# main.net
KiCad netlist of a schematic drawn in Altium Designer
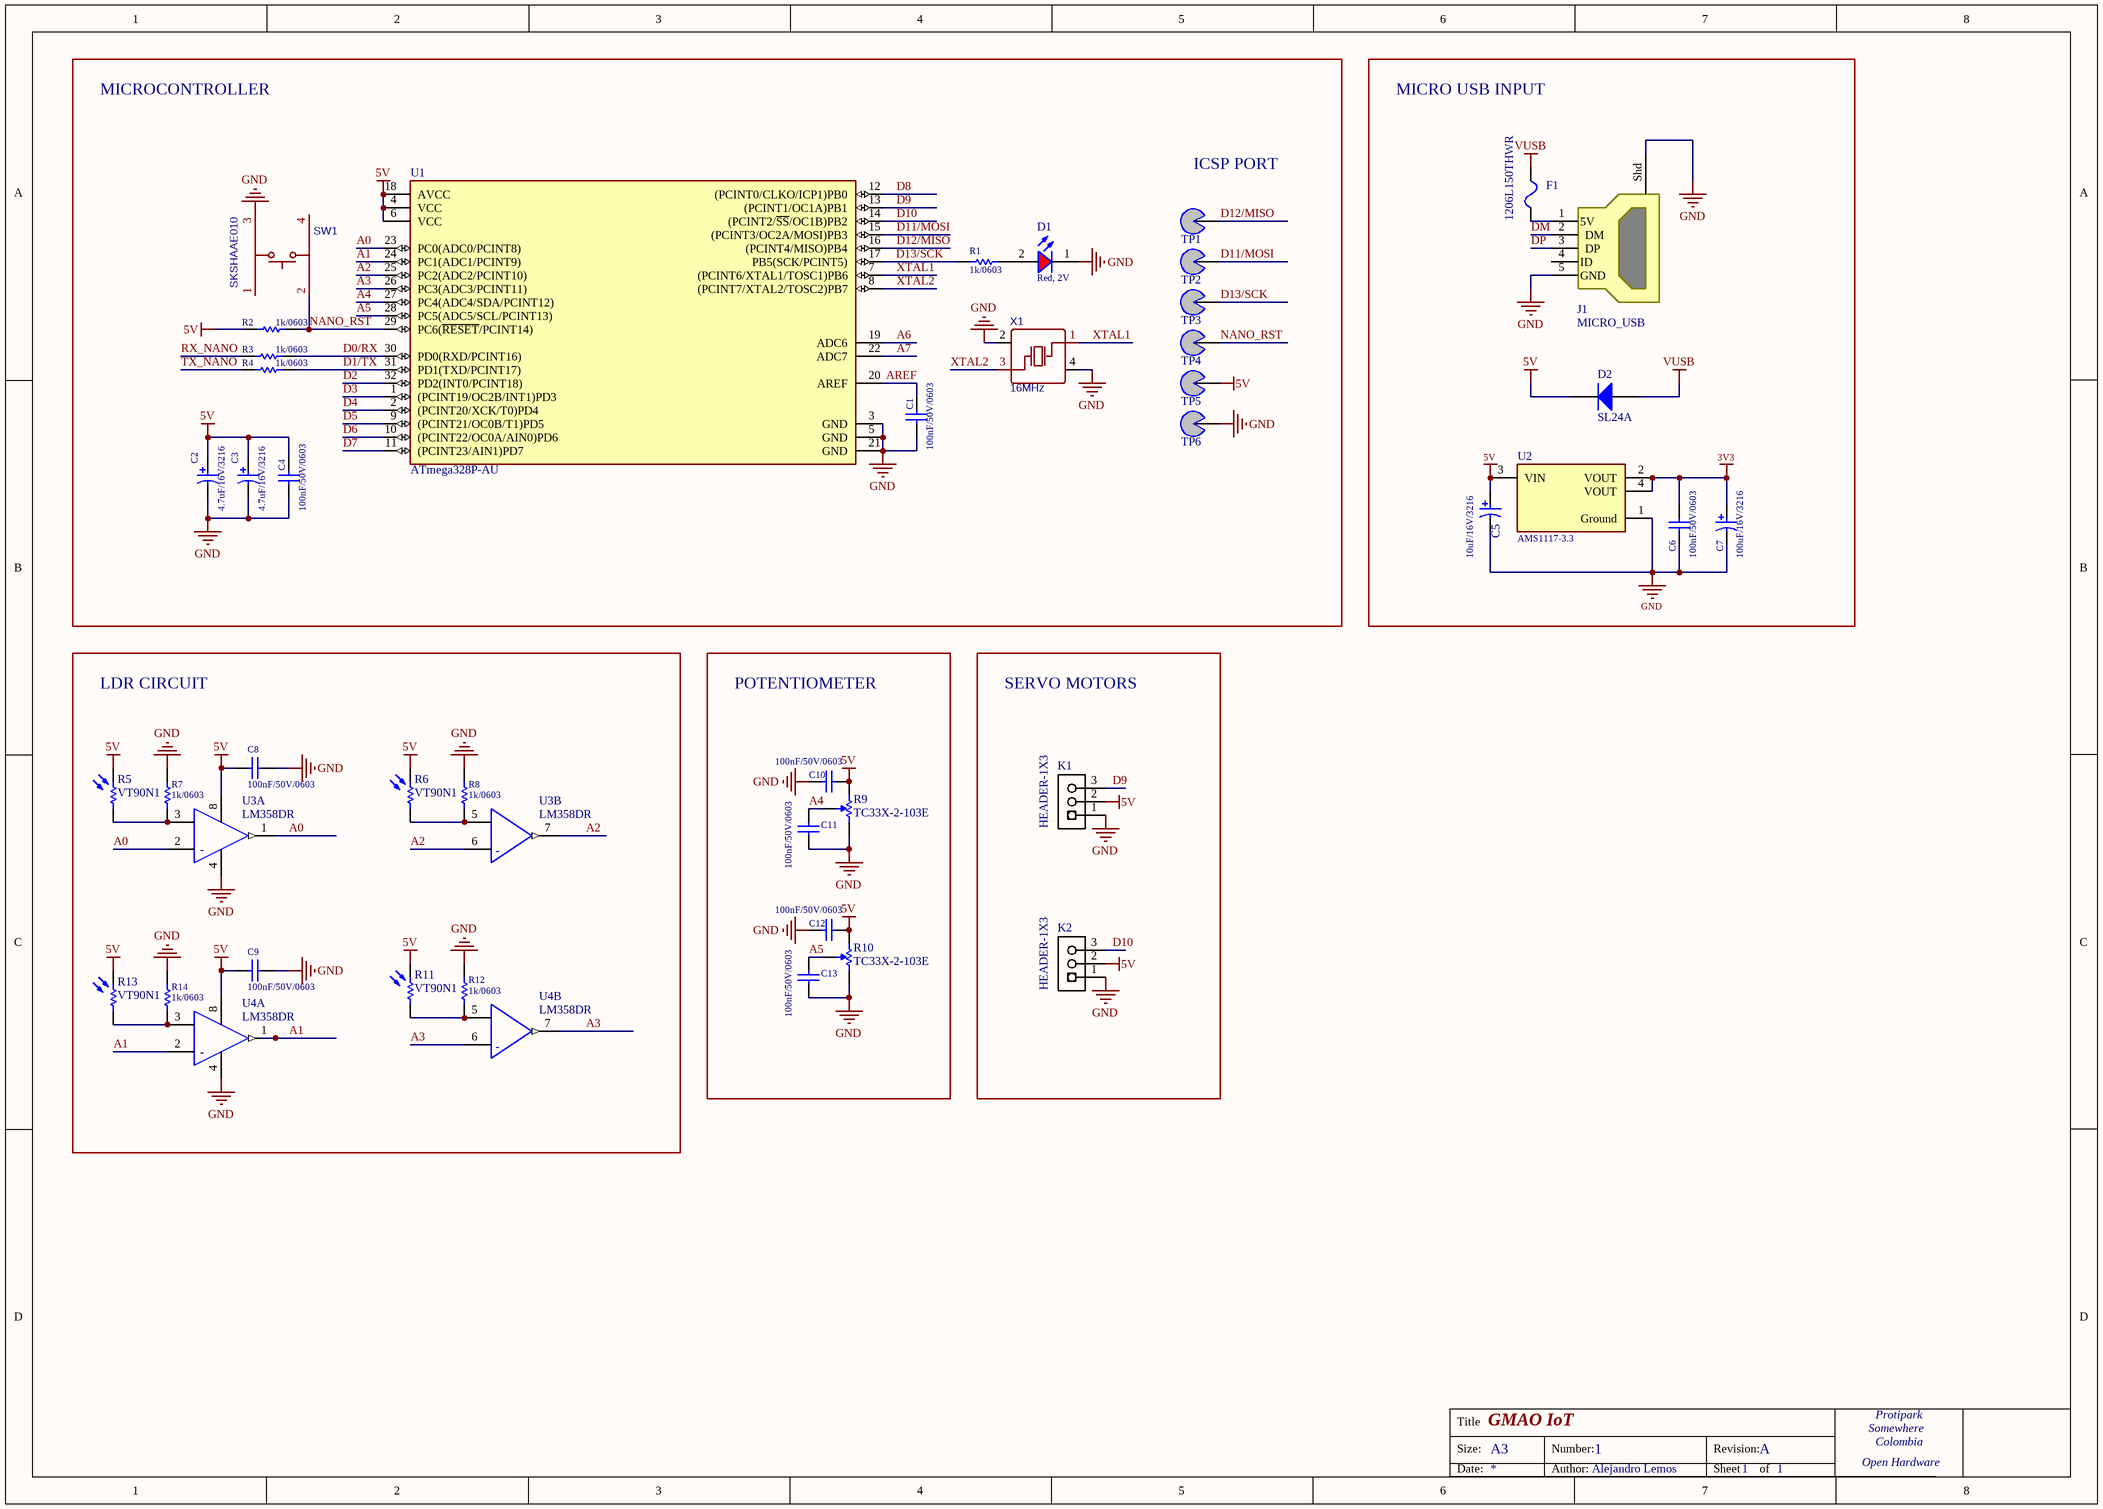
[diagram p0: main.SchDoc]

(export (version "E")
  (design (tool "Eeschema 10.0.6"))
  (components
    (comp (ref "C1")
      (value "100nF/50V/0603")
      (footprint "C0603_L")
      (libsource (lib "seitechs") (part "C_SMD"))
    )
    (comp (ref "C2")
      (value "4.7uF/16V/3216")
      (footprint "KEMT-T491-A_L")
      (description "Tantalum Capacitor, 2.2 uF, +/- 10%, 16 V, -55 to 125 degC, 2-Pin SMD, RoHS, Tape and Reel")
      (fields (field (name "VOLTAGE") "16VDC") (field (name "MANUFACTURER") "Kemet"))
      (libsource (lib "Altium Content Vault") (part "CAP-P-2"))
    )
    (comp (ref "C3")
      (value "4.7uF/16V/3216")
      (footprint "KEMT-T491-A_L")
      (description "Tantalum Capacitor, 2.2 uF, +/- 10%, 16 V, -55 to 125 degC, 2-Pin SMD, RoHS, Tape and Reel")
      (fields (field (name "VOLTAGE") "16VDC") (field (name "MANUFACTURER") "Kemet"))
      (libsource (lib "Altium Content Vault") (part "CAP-P-2"))
    )
    (comp (ref "C4")
      (value "100nF/50V/0603")
      (footprint "C0603_L")
      (libsource (lib "seitechs") (part "C_SMD"))
    )
    (comp (ref "C5")
      (value "10uF/16V/3216")
      (footprint "KEMT-T491-A_L")
      (description "Tantalum Capacitor, 2.2 uF, +/- 10%, 16 V, -55 to 125 degC, 2-Pin SMD, RoHS, Tape and Reel")
      (fields (field (name "VOLTAGE") "16VDC") (field (name "MANUFACTURER") "Kemet"))
      (libsource (lib "Altium Content Vault") (part "CAP-P-2"))
    )
    (comp (ref "C6")
      (value "100nF/50V/0603")
      (footprint "C0603_L")
      (libsource (lib "seitechs") (part "C_SMD"))
    )
    (comp (ref "C7")
      (value "100uF/16V/3216")
      (footprint "KEMT-T491-A_L")
      (description "Tantalum Capacitor, 2.2 uF, +/- 10%, 16 V, -55 to 125 degC, 2-Pin SMD, RoHS, Tape and Reel")
      (fields (field (name "VOLTAGE") "16VDC") (field (name "MANUFACTURER") "Kemet"))
      (libsource (lib "Altium Content Vault") (part "CAP-P-2"))
    )
    (comp (ref "C8")
      (value "100nF/50V/0603")
      (footprint "C0603_L")
      (libsource (lib "seitechs") (part "C_SMD"))
    )
    (comp (ref "C9")
      (value "100nF/50V/0603")
      (footprint "C0603_L")
      (libsource (lib "seitechs") (part "C_SMD"))
    )
    (comp (ref "C10")
      (value "100nF/50V/0603")
      (footprint "C0603_L")
      (libsource (lib "seitechs") (part "C_SMD"))
    )
    (comp (ref "C11")
      (value "100nF/50V/0603")
      (footprint "C0603_L")
      (libsource (lib "seitechs") (part "C_SMD"))
    )
    (comp (ref "C12")
      (value "100nF/50V/0603")
      (footprint "C0603_L")
      (libsource (lib "seitechs") (part "C_SMD"))
    )
    (comp (ref "C13")
      (value "100nF/50V/0603")
      (footprint "C0603_L")
      (libsource (lib "seitechs") (part "C_SMD"))
    )
    (comp (ref "D1")
      (value "Red, 2V")
      (footprint "WL-SMCW_0603_H=0.7mm")
      (description "WL-SMCW SMT Mono-color Chip LED Waterclear, size 0603, Red, 2V, 140deg")
      (fields (field (name "PART NUMBER") "150060RS75000") (field (name "PUBLISHER") "Wurth Elektronik"))
      (libsource (lib "Altium_WL-SMCW (rev20a)") (part "150060RS75000"))
    )
    (comp (ref "D2")
      (value "SL24A")
      (footprint "GESC-GAP3SLT33-214-2_V")
      (description "40V 2A 420mV @ 2A SMA(DO-214AC) Schottky Barrier Diodes (SBD) RoHS")
      (fields (field (name "MANUFACTURER") "GeneSiCSemiconductor"))
      (libsource (lib "Altium Content Vault") (part "D-AK-2"))
    )
    (comp (ref "F1")
      (value "1206L150THWR")
      (footprint "R1206_L")
      (description "FUSE PTC RESET 8V 1.50A 1206")
      (fields (field (name "MANUFACTURER") "Littelfuse Inc"))
      (libsource (lib "seitechs") (part "1206L150THWR"))
    )
    (comp (ref "J1")
      (value "MICRO_USB")
      (footprint "USB MICRO")
      (description "CONN USB MICRO B RECPT SMT R/A")
      (fields (field (name "MANUFACTURER") "FCI") (field (name "MANUFACTURER PART NUMBER") "10118194-0001LF"))
      (libsource (lib "seitechs") (part "MICRO_USB"))
    )
    (comp (ref "K1")
      (value "HEADER-1X3")
      (footprint "HEADER-1X3")
      (libsource (lib "vh_altium_library") (part "HEADER-1X3"))
    )
    (comp (ref "K2")
      (value "HEADER-1X3")
      (footprint "HEADER-1X3")
      (libsource (lib "vh_altium_library") (part "HEADER-1X3"))
    )
    (comp (ref "R1") (value "1k/0603") (footprint "R0603_N") (libsource (lib "seitechs") (part "R_SMD")))
    (comp (ref "R2") (value "1k/0603") (footprint "R0603_N") (libsource (lib "seitechs") (part "R_SMD")))
    (comp (ref "R3") (value "1k/0603") (footprint "R0603_N") (libsource (lib "seitechs") (part "R_SMD")))
    (comp (ref "R4") (value "1k/0603") (footprint "R0603_N") (libsource (lib "seitechs") (part "R_SMD")))
    (comp (ref "R5")
      (value "VT90N1")
      (footprint "EXCE-VT90N1")
      (description "Photoconductive Resistor, 200 kOhm, 100 V, 80 mW, -40 to 75 degC, 2-Pin THD, RoHS")
      (fields (field (name "MANUFACTURER") "Excelitas Technology"))
      (libsource (lib "Altium Content Vault") (part "PHOTO-RES-2"))
    )
    (comp (ref "R6")
      (value "VT90N1")
      (footprint "EXCE-VT90N1")
      (description "Photoconductive Resistor, 200 kOhm, 100 V, 80 mW, -40 to 75 degC, 2-Pin THD, RoHS")
      (fields (field (name "MANUFACTURER") "Excelitas Technology"))
      (libsource (lib "Altium Content Vault") (part "PHOTO-RES-2"))
    )
    (comp (ref "R7") (value "1k/0603") (footprint "R0603_N") (libsource (lib "seitechs") (part "R_SMD")))
    (comp (ref "R8") (value "1k/0603") (footprint "R0603_N") (libsource (lib "seitechs") (part "R_SMD")))
    (comp (ref "R9")
      (value "TC33X-2-103E")
      (footprint "BOUR-TC33X-2_V")
      (description "Trimming Potentiometer, 10000 Ohm, -40 to 100 degC, 3-Pin SMD, RoHS, Tape and Reel")
      (fields (field (name "TOLERANCE") "25%") (field (name "MANUFACTURER") "Bourns"))
      (libsource (lib "Altium Content Vault") (part "RES-ADJ-3_A"))
    )
    (comp (ref "R10")
      (value "TC33X-2-103E")
      (footprint "BOUR-TC33X-2_V")
      (description "Trimming Potentiometer, 10000 Ohm, -40 to 100 degC, 3-Pin SMD, RoHS, Tape and Reel")
      (fields (field (name "TOLERANCE") "25%") (field (name "MANUFACTURER") "Bourns"))
      (libsource (lib "Altium Content Vault") (part "RES-ADJ-3_A"))
    )
    (comp (ref "R11")
      (value "VT90N1")
      (footprint "EXCE-VT90N1")
      (description "Photoconductive Resistor, 200 kOhm, 100 V, 80 mW, -40 to 75 degC, 2-Pin THD, RoHS")
      (fields (field (name "MANUFACTURER") "Excelitas Technology"))
      (libsource (lib "Altium Content Vault") (part "PHOTO-RES-2"))
    )
    (comp (ref "R12") (value "1k/0603") (footprint "R0603_N") (libsource (lib "seitechs") (part "R_SMD")))
    (comp (ref "R13")
      (value "VT90N1")
      (footprint "EXCE-VT90N1")
      (description "Photoconductive Resistor, 200 kOhm, 100 V, 80 mW, -40 to 75 degC, 2-Pin THD, RoHS")
      (fields (field (name "MANUFACTURER") "Excelitas Technology"))
      (libsource (lib "Altium Content Vault") (part "PHOTO-RES-2"))
    )
    (comp (ref "R14") (value "1k/0603") (footprint "R0603_N") (libsource (lib "seitechs") (part "R_SMD")))
    (comp (ref "SW1")
      (value "SKSHAAE010")
      (footprint "SW-SMD_4P-L3.2-W2.9-P2.20-LS3.4")
      (description "SWITCH")
      (fields (field (name "BOM_SUPPLIER PART") "C262415") (field (name "CONTRIBUTOR") "LCSC"))
      (libsource (lib "seitechs") (part "SKSHAAE010"))
    )
    (comp (ref "TP1")
      (value "Test_Point")
      (footprint "TESTPOINT_PROG")
      (libsource (lib "seitechs") (part "Test_Point"))
    )
    (comp (ref "TP2")
      (value "Test_Point")
      (footprint "TESTPOINT_PROG")
      (libsource (lib "seitechs") (part "Test_Point"))
    )
    (comp (ref "TP3")
      (value "Test_Point")
      (footprint "TESTPOINT_PROG")
      (libsource (lib "seitechs") (part "Test_Point"))
    )
    (comp (ref "TP4")
      (value "Test_Point")
      (footprint "TESTPOINT_PROG")
      (libsource (lib "seitechs") (part "Test_Point"))
    )
    (comp (ref "TP5")
      (value "Test_Point")
      (footprint "TESTPOINT_PROG")
      (libsource (lib "seitechs") (part "Test_Point"))
    )
    (comp (ref "TP6")
      (value "Test_Point")
      (footprint "TESTPOINT_PROG")
      (libsource (lib "seitechs") (part "Test_Point"))
    )
    (comp (ref "U1")
      (value "ATmega328P-AU")
      (footprint "FP-32A-MFG")
      (description "IC MCU 8BIT 32KB FLASH 32TQFP")
      (fields
        (field (name "MANUFACTURER") "Microchip")
        (field (name "OCTOPART") "https://octopart.com/atmega328p-au-microchip-77760215")
      )
      (libsource (lib "Altium Content Vault") (part "f5fbdcb2c0c597ef7d3dd1575aef21a"))
    )
    (comp (ref "U2")
      (value "AMS1117-3.3")
      (footprint "FP-AMS1117-IPC_C")
      (description "LDO Voltage Regulators 1A, 3.3V")
      (fields
        (field (name "OCTOPART") "https://octopart.com/ams1117-3.3-advanced+monolithic+systems-25899300")
        (field (name "MANUFACTURER") "Advanced Monolithic Systems")
      )
      (libsource (lib "Altium Content Vault") (part "8bdbb5f8e77002000e30dd2845d0354"))
    )
    (comp (ref "U3")
      (value "LM358DR")
      (footprint "FP-D0008A-MFG")
      (description "IC OPAMP GP 2 CIRCUIT 8SOIC")
      (libsource (lib "Altium Content Vault") (part "0afdfe5f461d2cdd85604ff8654be97"))
    )
    (comp (ref "U4")
      (value "LM358DR")
      (footprint "FP-D0008A-MFG")
      (description "IC OPAMP GP 2 CIRCUIT 8SOIC")
      (libsource (lib "Altium Content Vault") (part "0afdfe5f461d2cdd85604ff8654be97"))
    )
    (comp (ref "X1")
      (value "16MHz")
      (footprint "CRYSTAL-SMD_4P-L3.2-W2.5-BL")
      (fields
        (field (name "BOM_MANUFACTURER PART") "X322516MOB4SI")
        (field (name "BOM_SUPPLIER PART") "C12668")
      )
      (libsource (lib "seitechs") (part "16MHz"))
    )
  )
  (nets
    (net (code "1") (name "/A0") (class "Default")
      (node (ref "U1") (pin "23") (pinfunction "PC0(ADC0/PCINT8)_23") (pintype "bidirectional"))
      (node (ref "U3") (pin "1") (pinfunction "1OUT_1") (pintype "output"))
      (node (ref "U3") (pin "2") (pinfunction "IN1-_2") (pintype "tri_state"))
    )
    (net (code "2") (name "/A1") (class "Default")
      (node (ref "U1") (pin "24") (pinfunction "PC1(ADC1/PCINT9)_24") (pintype "bidirectional"))
      (node (ref "U4") (pin "1") (pinfunction "1OUT_1") (pintype "output"))
      (node (ref "U4") (pin "2") (pinfunction "IN1-_2") (pintype "tri_state"))
    )
    (net (code "3") (name "/A2") (class "Default")
      (node (ref "U1") (pin "25") (pinfunction "PC2(ADC2/PCINT10)_25") (pintype "bidirectional"))
      (node (ref "U3") (pin "6") (pinfunction "IN2-_6") (pintype "tri_state"))
      (node (ref "U3") (pin "7") (pinfunction "2OUT_7") (pintype "output"))
    )
    (net (code "4") (name "/A3") (class "Default")
      (node (ref "U1") (pin "26") (pinfunction "PC3(ADC3/PCINT11)_26") (pintype "bidirectional"))
      (node (ref "U4") (pin "6") (pinfunction "IN2-_6") (pintype "tri_state"))
      (node (ref "U4") (pin "7") (pinfunction "2OUT_7") (pintype "output"))
    )
    (net (code "5") (name "/A4") (class "Default")
      (node (ref "C11") (pin "2") (pinfunction "2_2") (pintype "passive"))
      (node (ref "R9") (pin "2") (pinfunction "2_2") (pintype "passive"))
      (node (ref "U1") (pin "27") (pinfunction "PC4(ADC4/SDA/PCINT12)_27") (pintype "bidirectional"))
    )
    (net (code "6") (name "/A5") (class "Default")
      (node (ref "C13") (pin "2") (pinfunction "2_2") (pintype "passive"))
      (node (ref "R10") (pin "2") (pinfunction "2_2") (pintype "passive"))
      (node (ref "U1") (pin "28") (pinfunction "PC5(ADC5/SCL/PCINT13)_28") (pintype "bidirectional"))
    )
    (net (code "7") (name "/A6") (class "Default")
      (node (ref "U1") (pin "19") (pinfunction "ADC6_19") (pintype "power_in"))
    )
    (net (code "8") (name "/A7") (class "Default")
      (node (ref "U1") (pin "22") (pinfunction "ADC7_22") (pintype "passive"))
    )
    (net (code "9") (name "/AREF") (class "Default")
      (node (ref "C1") (pin "1") (pinfunction "1_1") (pintype "passive"))
      (node (ref "U1") (pin "20") (pinfunction "AREF_20") (pintype "passive"))
    )
    (net (code "10") (name "/D0{slash}RX") (class "Default")
      (node (ref "R3") (pin "2") (pinfunction "2_2") (pintype "passive"))
      (node (ref "U1") (pin "30") (pinfunction "PD0(RXD/PCINT16)_30") (pintype "bidirectional"))
    )
    (net (code "11") (name "/D1{slash}TX") (class "Default")
      (node (ref "R4") (pin "2") (pinfunction "2_2") (pintype "passive"))
      (node (ref "U1") (pin "31") (pinfunction "PD1(TXD/PCINT17)_31") (pintype "bidirectional"))
    )
    (net (code "12") (name "/D2") (class "Default")
      (node (ref "U1") (pin "32") (pinfunction "PD2(INT0/PCINT18)_32") (pintype "bidirectional"))
    )
    (net (code "13") (name "/D3") (class "Default")
      (node (ref "U1") (pin "1") (pinfunction "(PCINT19/OC2B/INT1)PD3_1") (pintype "bidirectional"))
    )
    (net (code "14") (name "/D4") (class "Default")
      (node (ref "U1") (pin "2") (pinfunction "(PCINT20/XCK/T0)PD4_2") (pintype "bidirectional"))
    )
    (net (code "15") (name "/D5") (class "Default")
      (node (ref "U1") (pin "9") (pinfunction "(PCINT21/OC0B/T1)PD5_9") (pintype "bidirectional"))
    )
    (net (code "16") (name "/D6") (class "Default")
      (node (ref "U1") (pin "10") (pinfunction "(PCINT22/OC0A/AIN0)PD6_10") (pintype "bidirectional"))
    )
    (net (code "17") (name "/D7") (class "Default")
      (node (ref "U1") (pin "11") (pinfunction "(PCINT23/AIN1)PD7_11") (pintype "bidirectional"))
    )
    (net (code "18") (name "/D8") (class "Default")
      (node (ref "U1") (pin "12") (pinfunction "(PCINT0/CLKO/ICP1)PB0_12") (pintype "bidirectional"))
    )
    (net (code "19") (name "/D9") (class "Default")
      (node (ref "K1") (pin "3") (pintype "passive"))
      (node (ref "U1") (pin "13") (pinfunction "(PCINT1/OC1A)PB1_13") (pintype "bidirectional"))
    )
    (net (code "20") (name "/D10") (class "Default")
      (node (ref "K2") (pin "3") (pintype "passive"))
      (node (ref "U1") (pin "14") (pinfunction "(PCINT2/~{SS}/OC1B)PB2_14") (pintype "bidirectional"))
    )
    (net (code "21") (name "/D11{slash}MOSI") (class "Default")
      (node (ref "TP2") (pin "0") (pinfunction "TP_0") (pintype "passive"))
      (node (ref "U1") (pin "15") (pinfunction "(PCINT3/OC2A/MOSI)PB3_15") (pintype "bidirectional"))
    )
    (net (code "22") (name "/D12{slash}MISO") (class "Default")
      (node (ref "TP1") (pin "0") (pinfunction "TP_0") (pintype "passive"))
      (node (ref "U1") (pin "16") (pinfunction "(PCINT4/MISO)PB4_16") (pintype "bidirectional"))
    )
    (net (code "23") (name "/D13{slash}SCK") (class "Default")
      (node (ref "R1") (pin "2") (pinfunction "2_2") (pintype "passive"))
      (node (ref "TP3") (pin "0") (pinfunction "TP_0") (pintype "passive"))
      (node (ref "U1") (pin "17") (pinfunction "PB5(SCK/PCINT5)_17") (pintype "bidirectional"))
    )
    (net (code "24") (name "/DM") (class "Default")
      (node (ref "J1") (pin "2") (pinfunction "DM_2") (pintype "passive"))
    )
    (net (code "25") (name "/DP") (class "Default")
      (node (ref "J1") (pin "3") (pinfunction "DP_3") (pintype "passive"))
    )
    (net (code "26") (name "/NANO_RST") (class "Default")
      (node (ref "R2") (pin "2") (pinfunction "2_2") (pintype "passive"))
      (node (ref "SW1") (pin "2") (pinfunction "2_2") (pintype "passive"))
      (node (ref "TP4") (pin "0") (pinfunction "TP_0") (pintype "passive"))
      (node (ref "U1") (pin "29") (pinfunction "PC6(~{RESET}/PCINT14)_29") (pintype "bidirectional"))
    )
    (net (code "27") (name "/RX_NANO") (class "Default")
      (node (ref "R3") (pin "1") (pinfunction "1_1") (pintype "passive"))
    )
    (net (code "28") (name "/TX_NANO") (class "Default")
      (node (ref "R4") (pin "1") (pinfunction "1_1") (pintype "passive"))
    )
    (net (code "29") (name "/XTAL1") (class "Default")
      (node (ref "U1") (pin "7") (pinfunction "(PCINT6/XTAL1/TOSC1)PB6_7") (pintype "bidirectional"))
      (node (ref "X1") (pin "1") (pinfunction "OSC1_1") (pintype "passive"))
    )
    (net (code "30") (name "/XTAL2") (class "Default")
      (node (ref "U1") (pin "8") (pinfunction "(PCINT7/XTAL2/TOSC2)PB7_8") (pintype "bidirectional"))
      (node (ref "X1") (pin "3") (pinfunction "OSC2_3") (pintype "passive"))
    )
    (net (code "31") (name "3V3") (class "Default")
      (node (ref "C6") (pin "2") (pinfunction "2_2") (pintype "passive"))
      (node (ref "C7") (pin "1") (pinfunction "1_1") (pintype "passive"))
      (node (ref "U2") (pin "2") (pinfunction "VOUT_2") (pintype "passive"))
      (node (ref "U2") (pin "4") (pinfunction "VOUT_4") (pintype "passive"))
    )
    (net (code "32") (name "5V") (class "Default")
      (node (ref "C10") (pin "2") (pinfunction "2_2") (pintype "passive"))
      (node (ref "C12") (pin "2") (pinfunction "2_2") (pintype "passive"))
      (node (ref "C2") (pin "1") (pinfunction "1_1") (pintype "passive"))
      (node (ref "C3") (pin "1") (pinfunction "1_1") (pintype "passive"))
      (node (ref "C4") (pin "2") (pinfunction "2_2") (pintype "passive"))
      (node (ref "C5") (pin "1") (pinfunction "1_1") (pintype "passive"))
      (node (ref "C8") (pin "2") (pinfunction "2_2") (pintype "passive"))
      (node (ref "C9") (pin "2") (pinfunction "2_2") (pintype "passive"))
      (node (ref "D2") (pin "2") (pinfunction "K_2") (pintype "passive"))
      (node (ref "K1") (pin "2") (pintype "passive"))
      (node (ref "K2") (pin "2") (pintype "passive"))
      (node (ref "R10") (pin "1") (pinfunction "1_1") (pintype "passive"))
      (node (ref "R11") (pin "2") (pinfunction "2_2") (pintype "passive"))
      (node (ref "R13") (pin "2") (pinfunction "2_2") (pintype "passive"))
      (node (ref "R2") (pin "1") (pinfunction "1_1") (pintype "passive"))
      (node (ref "R5") (pin "2") (pinfunction "2_2") (pintype "passive"))
      (node (ref "R6") (pin "2") (pinfunction "2_2") (pintype "passive"))
      (node (ref "R9") (pin "1") (pinfunction "1_1") (pintype "passive"))
      (node (ref "TP5") (pin "0") (pinfunction "TP_0") (pintype "passive"))
      (node (ref "U1") (pin "18") (pinfunction "AVCC_18") (pintype "power_in"))
      (node (ref "U1") (pin "4") (pinfunction "VCC_4") (pintype "power_in"))
      (node (ref "U1") (pin "6") (pinfunction "VCC_6") (pintype "power_in"))
      (node (ref "U2") (pin "3") (pinfunction "VIN_3") (pintype "power_in"))
      (node (ref "U3") (pin "8") (pinfunction "V+_8") (pintype "power_in"))
      (node (ref "U4") (pin "8") (pinfunction "V+_8") (pintype "power_in"))
    )
    (net (code "33") (name "GND") (class "Default")
      (node (ref "C1") (pin "2") (pinfunction "2_2") (pintype "passive"))
      (node (ref "C10") (pin "1") (pinfunction "1_1") (pintype "passive"))
      (node (ref "C11") (pin "1") (pinfunction "1_1") (pintype "passive"))
      (node (ref "C12") (pin "1") (pinfunction "1_1") (pintype "passive"))
      (node (ref "C13") (pin "1") (pinfunction "1_1") (pintype "passive"))
      (node (ref "C2") (pin "2") (pinfunction "2_2") (pintype "passive"))
      (node (ref "C3") (pin "2") (pinfunction "2_2") (pintype "passive"))
      (node (ref "C4") (pin "1") (pinfunction "1_1") (pintype "passive"))
      (node (ref "C5") (pin "2") (pinfunction "2_2") (pintype "passive"))
      (node (ref "C6") (pin "1") (pinfunction "1_1") (pintype "passive"))
      (node (ref "C7") (pin "2") (pinfunction "2_2") (pintype "passive"))
      (node (ref "C8") (pin "1") (pinfunction "1_1") (pintype "passive"))
      (node (ref "C9") (pin "1") (pinfunction "1_1") (pintype "passive"))
      (node (ref "D1") (pin "1") (pinfunction "K_1") (pintype "passive"))
      (node (ref "J1") (pin "5") (pinfunction "GND_5") (pintype "power_in"))
      (node (ref "J1") (pin "Shd") (pinfunction "6_Shd") (pintype "passive"))
      (node (ref "K1") (pin "1") (pintype "passive"))
      (node (ref "K2") (pin "1") (pintype "passive"))
      (node (ref "R10") (pin "3") (pinfunction "3_3") (pintype "passive"))
      (node (ref "R12") (pin "1") (pinfunction "1_1") (pintype "passive"))
      (node (ref "R14") (pin "1") (pinfunction "1_1") (pintype "passive"))
      (node (ref "R7") (pin "1") (pinfunction "1_1") (pintype "passive"))
      (node (ref "R8") (pin "1") (pinfunction "1_1") (pintype "passive"))
      (node (ref "R9") (pin "3") (pinfunction "3_3") (pintype "passive"))
      (node (ref "SW1") (pin "3") (pinfunction "3_3") (pintype "passive"))
      (node (ref "TP6") (pin "0") (pinfunction "TP_0") (pintype "passive"))
      (node (ref "U1") (pin "21") (pinfunction "GND_21") (pintype "power_in"))
      (node (ref "U1") (pin "3") (pinfunction "GND_3") (pintype "power_in"))
      (node (ref "U1") (pin "5") (pinfunction "GND_5") (pintype "power_in"))
      (node (ref "U2") (pin "1") (pinfunction "Ground_1") (pintype "power_in"))
      (node (ref "U3") (pin "4") (pinfunction "V-_4") (pintype "power_in"))
      (node (ref "U4") (pin "4") (pinfunction "V-_4") (pintype "power_in"))
      (node (ref "X1") (pin "2") (pinfunction "GND_2") (pintype "passive"))
      (node (ref "X1") (pin "4") (pinfunction "GND_4") (pintype "passive"))
    )
    (net (code "34") (name "Net-(D1-A)") (class "Default")
      (node (ref "D1") (pin "2") (pinfunction "A_2") (pintype "passive"))
      (node (ref "R1") (pin "1") (pinfunction "1_1") (pintype "passive"))
    )
    (net (code "35") (name "Net-(J1-5V)") (class "Default")
      (node (ref "F1") (pin "1") (pintype "passive"))
      (node (ref "J1") (pin "1") (pinfunction "5V_1") (pintype "power_in"))
    )
    (net (code "36") (name "Net-(U3A-IN1+)") (class "Default")
      (node (ref "R5") (pin "1") (pinfunction "1_1") (pintype "passive"))
      (node (ref "R7") (pin "2") (pinfunction "2_2") (pintype "passive"))
      (node (ref "U3") (pin "3") (pinfunction "IN1+_3") (pintype "tri_state"))
    )
    (net (code "37") (name "Net-(U3B-IN2+)") (class "Default")
      (node (ref "R6") (pin "1") (pinfunction "1_1") (pintype "passive"))
      (node (ref "R8") (pin "2") (pinfunction "2_2") (pintype "passive"))
      (node (ref "U3") (pin "5") (pinfunction "IN2+_5") (pintype "tri_state"))
    )
    (net (code "38") (name "Net-(U4A-IN1+)") (class "Default")
      (node (ref "R13") (pin "1") (pinfunction "1_1") (pintype "passive"))
      (node (ref "R14") (pin "2") (pinfunction "2_2") (pintype "passive"))
      (node (ref "U4") (pin "3") (pinfunction "IN1+_3") (pintype "tri_state"))
    )
    (net (code "39") (name "Net-(U4B-IN2+)") (class "Default")
      (node (ref "R11") (pin "1") (pinfunction "1_1") (pintype "passive"))
      (node (ref "R12") (pin "2") (pinfunction "2_2") (pintype "passive"))
      (node (ref "U4") (pin "5") (pinfunction "IN2+_5") (pintype "tri_state"))
    )
    (net (code "40") (name "VUSB") (class "Default")
      (node (ref "D2") (pin "1") (pinfunction "A_1") (pintype "passive"))
      (node (ref "F1") (pin "2") (pintype "passive"))
    )
    (net (code "41") (name "unconnected-(J1-ID-Pad4)") (class "Default")
      (node (ref "J1") (pin "4") (pinfunction "ID_4") (pintype "passive"))
    )
    (net (code "42") (name "unconnected-(SW1-Pad1)") (class "Default")
      (node (ref "SW1") (pin "1") (pinfunction "1_1") (pintype "passive"))
    )
    (net (code "43") (name "unconnected-(SW1-Pad4)") (class "Default")
      (node (ref "SW1") (pin "4") (pinfunction "4_4") (pintype "passive"))
    )
  )
)
